# schematic_square_wave_oscillator.net
KiCad netlist of a schematic drawn in EAGLE
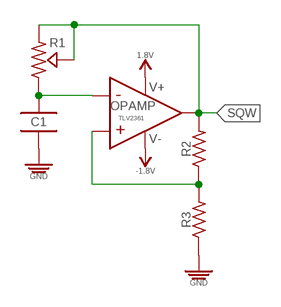
[diagram p0: schematic, sheet 1]

(export (version "E")
  (design (tool "Eeschema 10.0.6"))
  (components
    (comp (ref "C1")
      (value "0.1uF/50V")
      (footprint "eagle-import:CAPC1005X55_SMD-0402")
      (fields (field (name "MFR") "TDK Corporation") (field (name "MPN") "C1005X7R1H104K050BE"))
      (libsource (lib "eagle-import") (part "0.1UF_SMD-0402_50V-10%"))
    )
    (comp (ref "OPAMP")
      (value "TLV2361_GP_20MA_7MHZ")
      (footprint "eagle-import:SOT95P280X145-5")
      (fields (field (name "MFR") "Texas Instruments") (field (name "MPN") "TLV2361IDBVR"))
      (libsource (lib "eagle-import") (part "TLV2361_GP_20MA_7MHZ"))
    )
    (comp (ref "R1")
      (value "100K")
      (footprint "eagle-import:POTENTIOMETER_SQ-L5-W4.5-H2.3")
      (fields (field (name "MFR") "Nidec Copal Electronics") (field (name "MPN") "ST4ETB104"))
      (libsource (lib "eagle-import") (part "POTENTIOMETER_ST4ETB104_100K-1/4W-20%"))
    )
    (comp (ref "R2")
      (value "10K")
      (footprint "eagle-import:RESC1005X35_SMD-0402")
      (fields (field (name "MFR") "Yageo") (field (name "MPN") "RC0402JR-0710KP"))
      (libsource (lib "eagle-import") (part "10KΩ_SMD-0402_1/16W-5%"))
    )
    (comp (ref "R3")
      (value "10K")
      (footprint "eagle-import:RESC1005X35_SMD-0402")
      (fields (field (name "MFR") "Yageo") (field (name "MPN") "RC0402JR-0710KP"))
      (libsource (lib "eagle-import") (part "10KΩ_SMD-0402_1/16W-5%"))
    )
  )
  (nets
    (net (code "1") (name "-1.8V") (class "Default")
      (node (ref "OPAMP") (pin "2") (pinfunction "V-_2") (pintype "passive"))
    )
    (net (code "2") (name "1.8V") (class "Default")
      (node (ref "OPAMP") (pin "5") (pinfunction "V+_5") (pintype "passive"))
    )
    (net (code "3") (name "GND") (class "Default")
      (node (ref "C1") (pin "2") (pinfunction "2_2") (pintype "passive"))
      (node (ref "R3") (pin "1") (pinfunction "1_1") (pintype "passive"))
    )
    (net (code "4") (name "Net-(OPAMP-IN+)") (class "Default")
      (node (ref "OPAMP") (pin "1") (pinfunction "IN+_1") (pintype "input"))
      (node (ref "R2") (pin "1") (pinfunction "1_1") (pintype "passive"))
      (node (ref "R3") (pin "2") (pinfunction "2_2") (pintype "passive"))
    )
    (net (code "5") (name "Net-(OPAMP-IN-)") (class "Default")
      (node (ref "C1") (pin "1") (pinfunction "1_1") (pintype "passive"))
      (node (ref "OPAMP") (pin "3") (pinfunction "IN-_3") (pintype "input"))
      (node (ref "R1") (pin "3") (pinfunction "CW_3") (pintype "passive"))
    )
    (net (code "6") (name "SQW") (class "Default")
      (node (ref "OPAMP") (pin "4") (pinfunction "OUT_4") (pintype "output"))
      (node (ref "R1") (pin "1") (pinfunction "CCW_1") (pintype "passive"))
      (node (ref "R1") (pin "2") (pinfunction "S_2") (pintype "passive"))
      (node (ref "R2") (pin "2") (pinfunction "2_2") (pintype "passive"))
    )
  )
)
